# Schematic_of_PCB.net
KiCad netlist of a schematic drawn in Altium Designer
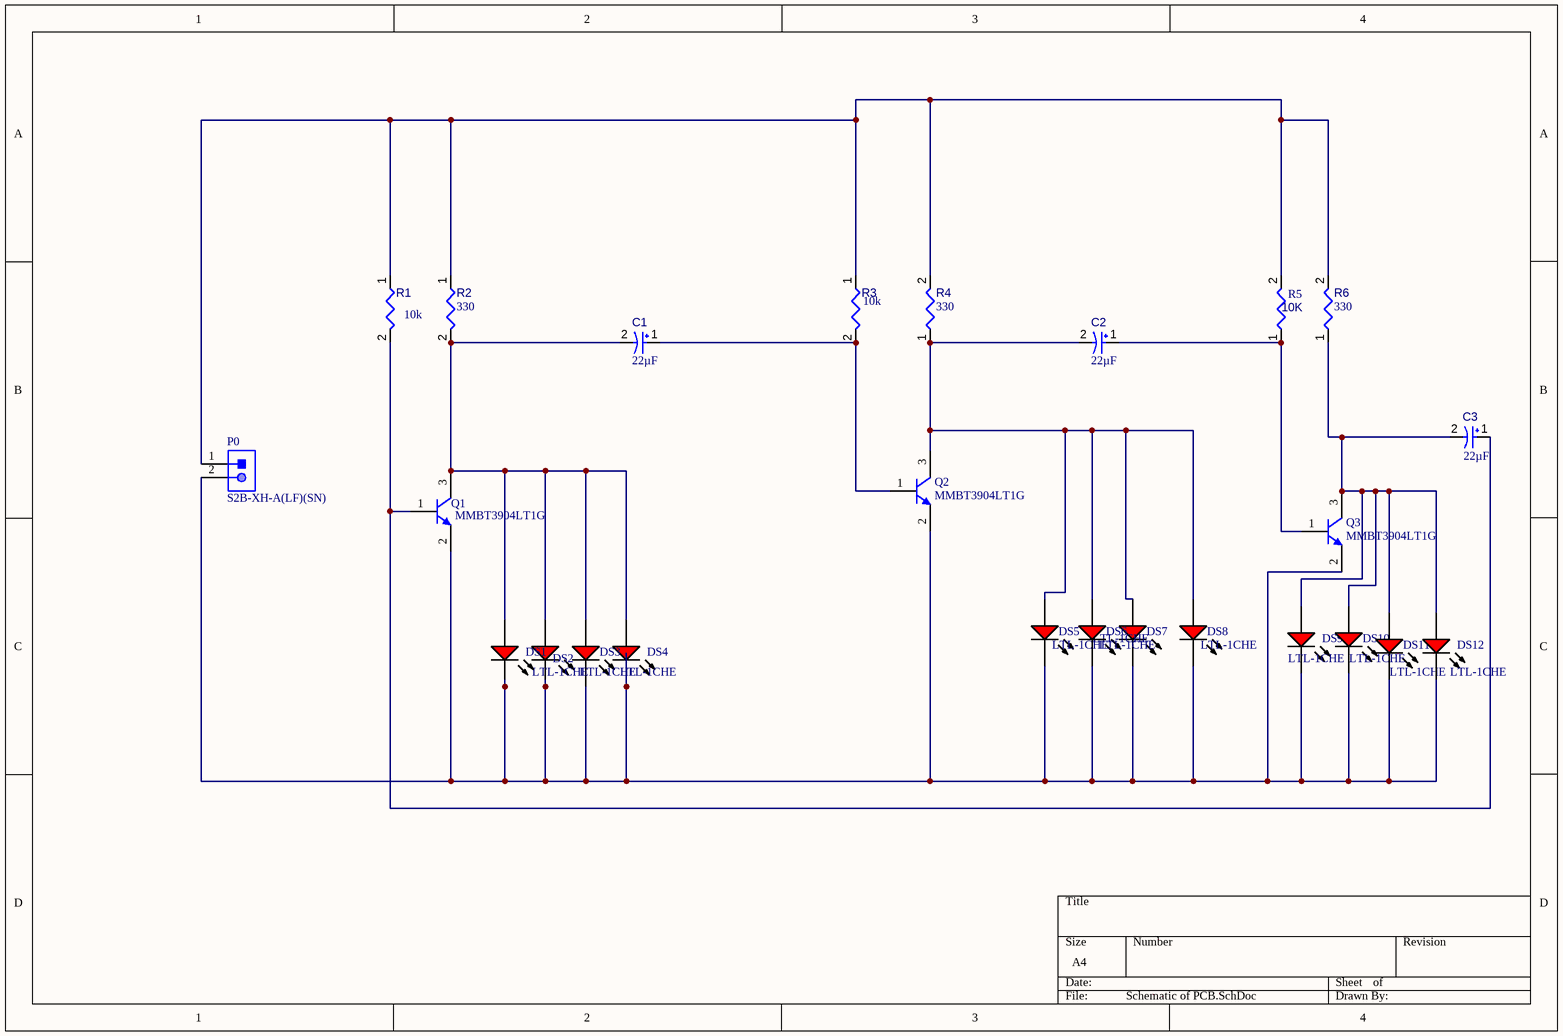
[diagram p0: Schematic of PCB.SchDoc]

(export (version "E")
  (design (tool "Eeschema 10.0.6"))
  (components
    (comp (ref "10K")
      (value "R5")
      (footprint "RESA60-630X240")
      (description "Axial Resistor, 10 KOhm, +/- 1%, 0.25 W, -55 to 155 degC, 2-Pin THD, RoHS, Bulk")
      (fields (field (name "TOLERANCE") "1%") (field (name "POWER") "250mW"))
      (libsource (lib "Sumon Boiddo") (part "RES-2"))
    )
    (comp (ref "C1")
      (value "22µF")
      (footprint "CAPPR55-200-1100X500X1200")
      (description "Aluminum Electrolytic Capacitor, 22 uF, +/- 20%, 50 V, -40 to 85 degC, 2-Pin THD, RoHS, Bulk")
      (fields (field (name "MANUFACTURER") "Panasonic") (field (name "TOLERANCE") "20%"))
      (libsource (lib "Sumon Boiddo") (part "CAP-P-2"))
    )
    (comp (ref "C2")
      (value "22µF")
      (footprint "CAPPR55-200-1100X500X1200")
      (description "Aluminum Electrolytic Capacitor, 22 uF, +/- 20%, 50 V, -40 to 85 degC, 2-Pin THD, RoHS, Bulk")
      (fields (field (name "MANUFACTURER") "Panasonic") (field (name "TOLERANCE") "20%"))
      (libsource (lib "Sumon Boiddo") (part "CAP-P-2"))
    )
    (comp (ref "C3")
      (value "22µF")
      (footprint "CAPPR55-200-1100X500X1200")
      (description "Aluminum Electrolytic Capacitor, 22 uF, +/- 20%, 50 V, -40 to 85 degC, 2-Pin THD, RoHS, Bulk")
      (fields (field (name "MANUFACTURER") "Panasonic") (field (name "TOLERANCE") "20%"))
      (libsource (lib "Sumon Boiddo") (part "CAP-P-2"))
    )
    (comp (ref "DS1")
      (value "~")
      (footprint "INDPR60-254-520X380X650")
      (description "LED Uni-Color Red, 100 mW, 30 mA, -55 to 100 degC, 2-Pin THD, RoHS, Bulk")
      (fields (field (name "MANUFACTURER") "Lite-On"))
      (libsource (lib "Sumon Boiddo") (part "LED-RED-AK-2"))
    )
    (comp (ref "DS2")
      (value "LTL-1CHE")
      (footprint "INDPR60-254-520X380X650")
      (description "LED Uni-Color Red, 100 mW, 30 mA, -55 to 100 degC, 2-Pin THD, RoHS, Bulk")
      (fields (field (name "MANUFACTURER") "Lite-On"))
      (libsource (lib "Sumon Boiddo") (part "LED-RED-AK-2"))
    )
    (comp (ref "DS3")
      (value "LTL-1CHE")
      (footprint "INDPR60-254-520X380X650")
      (description "LED Uni-Color Red, 100 mW, 30 mA, -55 to 100 degC, 2-Pin THD, RoHS, Bulk")
      (fields (field (name "MANUFACTURER") "Lite-On"))
      (libsource (lib "Sumon Boiddo") (part "LED-RED-AK-2"))
    )
    (comp (ref "DS4")
      (value "LTL-1CHE")
      (footprint "INDPR60-254-520X380X650")
      (description "LED Uni-Color Red, 100 mW, 30 mA, -55 to 100 degC, 2-Pin THD, RoHS, Bulk")
      (fields (field (name "MANUFACTURER") "Lite-On"))
      (libsource (lib "Sumon Boiddo") (part "LED-RED-AK-2"))
    )
    (comp (ref "DS5")
      (value "LTL-1CHE")
      (footprint "INDPR60-254-520X380X650")
      (description "LED Uni-Color Red, 100 mW, 30 mA, -55 to 100 degC, 2-Pin THD, RoHS, Bulk")
      (fields (field (name "MANUFACTURER") "Lite-On"))
      (libsource (lib "Sumon Boiddo") (part "LED-RED-AK-2"))
    )
    (comp (ref "DS6")
      (value "LTL-1CHE")
      (footprint "INDPR60-254-520X380X650")
      (description "LED Uni-Color Red, 100 mW, 30 mA, -55 to 100 degC, 2-Pin THD, RoHS, Bulk")
      (fields (field (name "MANUFACTURER") "Lite-On"))
      (libsource (lib "Sumon Boiddo") (part "LED-RED-AK-2"))
    )
    (comp (ref "DS7")
      (value "LTL-1CHE")
      (footprint "INDPR60-254-520X380X650")
      (description "LED Uni-Color Red, 100 mW, 30 mA, -55 to 100 degC, 2-Pin THD, RoHS, Bulk")
      (fields (field (name "MANUFACTURER") "Lite-On"))
      (libsource (lib "Sumon Boiddo") (part "LED-RED-AK-2"))
    )
    (comp (ref "DS8")
      (value "LTL-1CHE")
      (footprint "INDPR60-254-520X380X650")
      (description "LED Uni-Color Red, 100 mW, 30 mA, -55 to 100 degC, 2-Pin THD, RoHS, Bulk")
      (fields (field (name "MANUFACTURER") "Lite-On"))
      (libsource (lib "Sumon Boiddo") (part "LED-RED-AK-2"))
    )
    (comp (ref "DS9")
      (value "LTL-1CHE")
      (footprint "INDPR60-254-520X380X650")
      (description "LED Uni-Color Red, 100 mW, 30 mA, -55 to 100 degC, 2-Pin THD, RoHS, Bulk")
      (fields (field (name "MANUFACTURER") "Lite-On"))
      (libsource (lib "Sumon Boiddo") (part "LED-RED-AK-2"))
    )
    (comp (ref "DS10")
      (value "LTL-1CHE")
      (footprint "INDPR60-254-520X380X650")
      (description "LED Uni-Color Red, 100 mW, 30 mA, -55 to 100 degC, 2-Pin THD, RoHS, Bulk")
      (fields (field (name "MANUFACTURER") "Lite-On"))
      (libsource (lib "Sumon Boiddo") (part "LED-RED-AK-2"))
    )
    (comp (ref "DS11")
      (value "LTL-1CHE")
      (footprint "INDPR60-254-520X380X650")
      (description "LED Uni-Color Red, 100 mW, 30 mA, -55 to 100 degC, 2-Pin THD, RoHS, Bulk")
      (fields (field (name "MANUFACTURER") "Lite-On"))
      (libsource (lib "Sumon Boiddo") (part "LED-RED-AK-2"))
    )
    (comp (ref "DS12")
      (value "LTL-1CHE")
      (footprint "INDPR60-254-520X380X650")
      (description "LED Uni-Color Red, 100 mW, 30 mA, -55 to 100 degC, 2-Pin THD, RoHS, Bulk")
      (fields (field (name "MANUFACTURER") "Lite-On"))
      (libsource (lib "Sumon Boiddo") (part "LED-RED-AK-2"))
    )
    (comp (ref "P0")
      (value "S2B-XH-A(LF)(SN)")
      (footprint "JST-S2B-XH-A(LF)(SN)_V")
      (fields (field (name "MANUFACTURER") "JST"))
      (libsource (lib "Sumon Boiddo") (part "CN-1P-M-R2"))
    )
    (comp (ref "Q1")
      (value "MMBT3904LT1G")
      (footprint "ONSC-SOT-23-3-318-08_V")
      (fields (field (name "MANUFACTURER") "ON Semiconductor") (field (name "POWER") "225mW"))
      (libsource (lib "Sumon Boiddo") (part "ONSC-NPN-B1E2C3-3"))
    )
    (comp (ref "Q2")
      (value "MMBT3904LT1G")
      (footprint "ONSC-SOT-23-3-318-08_V")
      (fields (field (name "MANUFACTURER") "ON Semiconductor") (field (name "POWER") "225mW"))
      (libsource (lib "Sumon Boiddo") (part "ONSC-NPN-B1E2C3-3"))
    )
    (comp (ref "Q3")
      (value "MMBT3904LT1G")
      (footprint "ONSC-SOT-23-3-318-08_V")
      (fields (field (name "MANUFACTURER") "ON Semiconductor") (field (name "POWER") "225mW"))
      (libsource (lib "Sumon Boiddo") (part "ONSC-NPN-B1E2C3-3"))
    )
    (comp (ref "R1")
      (value "10k")
      (footprint "RESA60-630X240")
      (description "Axial Resistor, 10 KOhm, +/- 1%, 0.25 W, -55 to 155 degC, 2-Pin THD, RoHS, Bulk")
      (fields (field (name "TOLERANCE") "1%") (field (name "POWER") "250mW"))
      (libsource (lib "Sumon Boiddo") (part "RES-2"))
    )
    (comp (ref "R2")
      (value "330")
      (footprint "RESC0402(1005)_L")
      (description "Chip Resistor, 330 Ohms, +/-5 %, 63 mW, -55 to 155 degC, 0402")
      (fields (field (name "POWER") "63mW") (field (name "TOLERANCE") "5%"))
      (libsource (lib "Sumon Boiddo") (part "RES-2"))
    )
    (comp (ref "R3")
      (value "10k")
      (footprint "RESA60-630X240")
      (description "Axial Resistor, 10 KOhm, +/- 1%, 0.25 W, -55 to 155 degC, 2-Pin THD, RoHS, Bulk")
      (fields (field (name "TOLERANCE") "1%") (field (name "POWER") "250mW"))
      (libsource (lib "Sumon Boiddo") (part "RES-2"))
    )
    (comp (ref "R4")
      (value "330")
      (footprint "RESA60-630X240")
      (description "Axial Resistor, 10 KOhm, +/- 1%, 0.25 W, -55 to 155 degC, 2-Pin THD, RoHS, Bulk")
      (fields (field (name "TOLERANCE") "1%") (field (name "POWER") "250mW"))
      (libsource (lib "Sumon Boiddo") (part "RES-2"))
    )
    (comp (ref "R6")
      (value "330")
      (footprint "RESA60-630X240")
      (description "Axial Resistor, 10 KOhm, +/- 1%, 0.25 W, -55 to 155 degC, 2-Pin THD, RoHS, Bulk")
      (fields (field (name "TOLERANCE") "1%") (field (name "POWER") "250mW"))
      (libsource (lib "Sumon Boiddo") (part "RES-2"))
    )
  )
  (nets
    (net (code "1") (name "Net-(10K-Pad2)") (class "Default")
      (node (ref "10K") (pin "2") (pinfunction "2_2") (pintype "passive"))
      (node (ref "P0") (pin "1") (pinfunction "1_1") (pintype "passive"))
      (node (ref "R1") (pin "1") (pinfunction "1_1") (pintype "passive"))
      (node (ref "R2") (pin "1") (pinfunction "1_1") (pintype "passive"))
      (node (ref "R3") (pin "1") (pinfunction "1_1") (pintype "passive"))
      (node (ref "R4") (pin "2") (pinfunction "2_2") (pintype "passive"))
      (node (ref "R6") (pin "2") (pinfunction "2_2") (pintype "passive"))
    )
    (net (code "2") (name "Net-(DS1-A)") (class "Default")
      (node (ref "C1") (pin "2") (pinfunction "2_2") (pintype "passive"))
      (node (ref "DS1") (pin "1") (pinfunction "A_1") (pintype "passive"))
      (node (ref "DS2") (pin "1") (pinfunction "A_1") (pintype "passive"))
      (node (ref "DS3") (pin "1") (pinfunction "A_1") (pintype "passive"))
      (node (ref "DS4") (pin "1") (pinfunction "A_1") (pintype "passive"))
      (node (ref "Q1") (pin "3") (pinfunction "C_3") (pintype "passive"))
      (node (ref "R2") (pin "2") (pinfunction "2_2") (pintype "passive"))
    )
    (net (code "3") (name "Net-(DS1-K)") (class "Default")
      (node (ref "DS1") (pin "2") (pinfunction "K_2") (pintype "passive"))
      (node (ref "DS10") (pin "2") (pinfunction "K_2") (pintype "passive"))
      (node (ref "DS11") (pin "2") (pinfunction "K_2") (pintype "passive"))
      (node (ref "DS12") (pin "2") (pinfunction "K_2") (pintype "passive"))
      (node (ref "DS2") (pin "2") (pinfunction "K_2") (pintype "passive"))
      (node (ref "DS3") (pin "2") (pinfunction "K_2") (pintype "passive"))
      (node (ref "DS4") (pin "2") (pinfunction "K_2") (pintype "passive"))
      (node (ref "DS5") (pin "2") (pinfunction "K_2") (pintype "passive"))
      (node (ref "DS6") (pin "2") (pinfunction "K_2") (pintype "passive"))
      (node (ref "DS7") (pin "2") (pinfunction "K_2") (pintype "passive"))
      (node (ref "DS8") (pin "2") (pinfunction "K_2") (pintype "passive"))
      (node (ref "DS9") (pin "2") (pinfunction "K_2") (pintype "passive"))
      (node (ref "P0") (pin "2") (pinfunction "2_2") (pintype "passive"))
      (node (ref "Q1") (pin "2") (pinfunction "E_2") (pintype "passive"))
      (node (ref "Q2") (pin "2") (pinfunction "E_2") (pintype "passive"))
      (node (ref "Q3") (pin "2") (pinfunction "E_2") (pintype "passive"))
    )
    (net (code "4") (name "Net-(DS5-A)") (class "Default")
      (node (ref "C2") (pin "2") (pinfunction "2_2") (pintype "passive"))
      (node (ref "DS5") (pin "1") (pinfunction "A_1") (pintype "passive"))
      (node (ref "DS6") (pin "1") (pinfunction "A_1") (pintype "passive"))
      (node (ref "DS7") (pin "1") (pinfunction "A_1") (pintype "passive"))
      (node (ref "DS8") (pin "1") (pinfunction "A_1") (pintype "passive"))
      (node (ref "Q2") (pin "3") (pinfunction "C_3") (pintype "passive"))
      (node (ref "R4") (pin "1") (pinfunction "1_1") (pintype "passive"))
    )
    (net (code "5") (name "Net-(DS10-A)") (class "Default")
      (node (ref "C3") (pin "2") (pinfunction "2_2") (pintype "passive"))
      (node (ref "DS10") (pin "1") (pinfunction "A_1") (pintype "passive"))
      (node (ref "DS11") (pin "1") (pinfunction "A_1") (pintype "passive"))
      (node (ref "DS12") (pin "1") (pinfunction "A_1") (pintype "passive"))
      (node (ref "DS9") (pin "1") (pinfunction "A_1") (pintype "passive"))
      (node (ref "Q3") (pin "3") (pinfunction "C_3") (pintype "passive"))
      (node (ref "R6") (pin "1") (pinfunction "1_1") (pintype "passive"))
    )
    (net (code "6") (name "Net-(Q1-B)") (class "Default")
      (node (ref "C3") (pin "1") (pinfunction "1_1") (pintype "passive"))
      (node (ref "Q1") (pin "1") (pinfunction "B_1") (pintype "passive"))
      (node (ref "R1") (pin "2") (pinfunction "2_2") (pintype "passive"))
    )
    (net (code "7") (name "Net-(Q2-B)") (class "Default")
      (node (ref "C1") (pin "1") (pinfunction "1_1") (pintype "passive"))
      (node (ref "Q2") (pin "1") (pinfunction "B_1") (pintype "passive"))
      (node (ref "R3") (pin "2") (pinfunction "2_2") (pintype "passive"))
    )
    (net (code "8") (name "Net-(Q3-B)") (class "Default")
      (node (ref "10K") (pin "1") (pinfunction "1_1") (pintype "passive"))
      (node (ref "C2") (pin "1") (pinfunction "1_1") (pintype "passive"))
      (node (ref "Q3") (pin "1") (pinfunction "B_1") (pintype "passive"))
    )
  )
)
